# Mega8515_flasher_v2.net
KiCad netlist of a schematic drawn in EAGLE
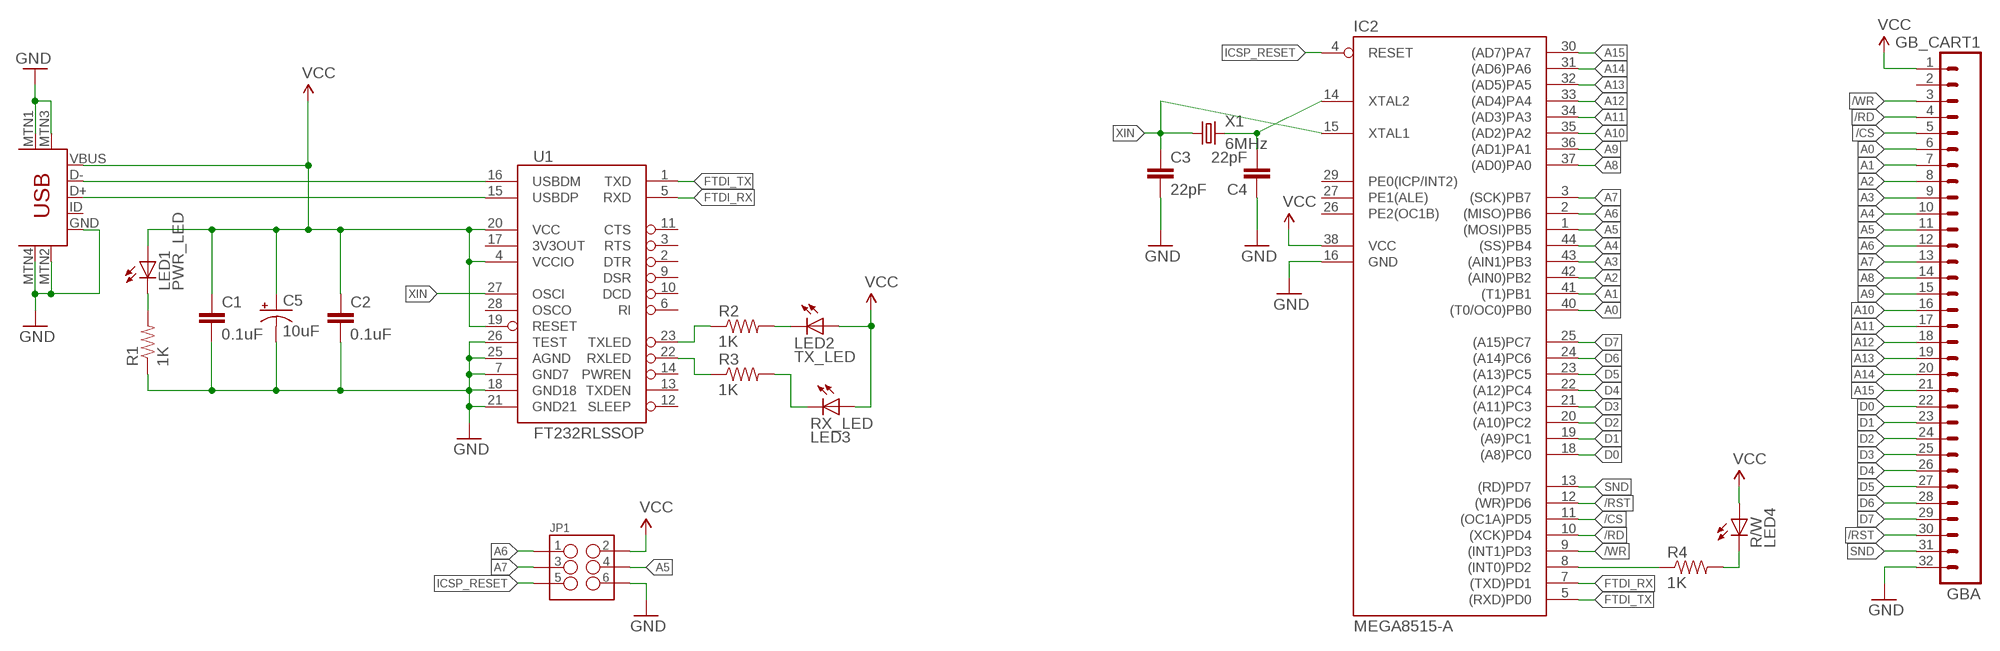
[diagram p0: schematic, sheet 1]

(export (version "E")
  (design (tool "Eeschema 10.0.6"))
  (components
    (comp (ref "C1")
      (value "0.1uF")
      (footprint "eagle-import:1206")
      (libsource (lib "eagle-import") (part "CAP1206"))
    )
    (comp (ref "C2")
      (value "0.1uF")
      (footprint "eagle-import:1206")
      (libsource (lib "eagle-import") (part "CAP1206"))
    )
    (comp (ref "C3")
      (value "22pF")
      (footprint "eagle-import:0805")
      (libsource (lib "eagle-import") (part "CAP0805"))
    )
    (comp (ref "C4")
      (value "22pF")
      (footprint "eagle-import:0805")
      (libsource (lib "eagle-import") (part "CAP0805"))
    )
    (comp (ref "C5")
      (value "10uF")
      (footprint "eagle-import:EIA3216")
      (libsource (lib "eagle-import") (part "10UF-TANT"))
    )
    (comp (ref "GBA")
      (value "GB_CART1")
      (footprint "eagle-import:GB_CART_1")
      (libsource (lib "eagle-import") (part "GB_CART1"))
    )
    (comp (ref "IC2")
      (value "MEGA8515-A")
      (footprint "eagle-import:TQFP44")
      (fields (field (name "MPN") "ATMEGA8515-16AU"))
      (libsource (lib "eagle-import") (part "MEGA8515-A"))
    )
    (comp (ref "JP1")
      (value "SPARKFUN-CONNECTORS_M03X2SMT")
      (footprint "eagle-import:SPARKFUN-CONNECTORS_2X3_SMT_POSTS")
      (libsource (lib "eagle-import") (part "SPARKFUN-CONNECTORS_M03X2SMT"))
    )
    (comp (ref "LED1")
      (value "PWR_LED")
      (footprint "eagle-import:LED-1206")
      (libsource (lib "eagle-import") (part "LED1206"))
    )
    (comp (ref "LED2")
      (value "TX_LED")
      (footprint "eagle-import:LED-1206")
      (libsource (lib "eagle-import") (part "LED1206"))
    )
    (comp (ref "R/W")
      (value "LED4")
      (footprint "eagle-import:LED-1206")
      (libsource (lib "eagle-import") (part "LED1206"))
    )
    (comp (ref "R1")
      (value "1K")
      (footprint "eagle-import:1206")
      (libsource (lib "eagle-import") (part "RESISTOR1206"))
    )
    (comp (ref "R2")
      (value "1K")
      (footprint "eagle-import:1206")
      (libsource (lib "eagle-import") (part "RESISTOR1206"))
    )
    (comp (ref "R3")
      (value "1K")
      (footprint "eagle-import:1206")
      (libsource (lib "eagle-import") (part "RESISTOR1206"))
    )
    (comp (ref "R4")
      (value "1K")
      (footprint "eagle-import:1206")
      (libsource (lib "eagle-import") (part "RESISTOR1206"))
    )
    (comp (ref "RX_LED")
      (value "LED3")
      (footprint "eagle-import:LED-1206")
      (libsource (lib "eagle-import") (part "LED1206"))
    )
    (comp (ref "U1")
      (value "FT232RLSSOP")
      (footprint "eagle-import:SSOP28DB")
      (libsource (lib "eagle-import") (part "FT232RLSSOP"))
    )
    (comp (ref "USB")
      (value "USB-MINIB-5PIN")
      (footprint "eagle-import:USB-MINIB")
      (libsource (lib "eagle-import") (part "USB-MINIB-5PIN"))
    )
    (comp (ref "X1")
      (value "6MHz")
      (footprint "eagle-import:SPARKFUN-FREQCTRL_CRYSTAL-SMD-11.8X5.5")
      (libsource (lib "eagle-import") (part "SPARKFUN-FREQCTRL_CRYSTAL"))
    )
  )
  (nets
    (net (code "1") (name "A0") (class "Default")
      (node (ref "GBA") (pin "6") (pinfunction "6_6") (pintype "passive"))
      (node (ref "IC2") (pin "40") (pinfunction "(T0/OC0)PB0_40") (pintype "bidirectional"))
    )
    (net (code "2") (name "A1") (class "Default")
      (node (ref "GBA") (pin "7") (pinfunction "7_7") (pintype "passive"))
      (node (ref "IC2") (pin "41") (pinfunction "(T1)PB1_41") (pintype "bidirectional"))
    )
    (net (code "3") (name "A2") (class "Default")
      (node (ref "GBA") (pin "8") (pinfunction "8_8") (pintype "passive"))
      (node (ref "IC2") (pin "42") (pinfunction "(AIN0)PB2_42") (pintype "bidirectional"))
    )
    (net (code "4") (name "A3") (class "Default")
      (node (ref "GBA") (pin "9") (pinfunction "9_9") (pintype "passive"))
      (node (ref "IC2") (pin "43") (pinfunction "(AIN1)PB3_43") (pintype "bidirectional"))
    )
    (net (code "5") (name "A4") (class "Default")
      (node (ref "GBA") (pin "10") (pinfunction "10_10") (pintype "passive"))
      (node (ref "IC2") (pin "44") (pinfunction "(SS)PB4_44") (pintype "bidirectional"))
    )
    (net (code "6") (name "A5") (class "Default")
      (node (ref "GBA") (pin "11") (pinfunction "11_11") (pintype "passive"))
      (node (ref "IC2") (pin "1") (pinfunction "(MOSI)PB5_1") (pintype "bidirectional"))
      (node (ref "JP1") (pin "4") (pinfunction "4_4") (pintype "bidirectional"))
    )
    (net (code "7") (name "A6") (class "Default")
      (node (ref "GBA") (pin "12") (pinfunction "12_12") (pintype "passive"))
      (node (ref "IC2") (pin "2") (pinfunction "(MISO)PB6_2") (pintype "bidirectional"))
      (node (ref "JP1") (pin "1") (pinfunction "1_1") (pintype "bidirectional"))
    )
    (net (code "8") (name "A7") (class "Default")
      (node (ref "GBA") (pin "13") (pinfunction "13_13") (pintype "passive"))
      (node (ref "IC2") (pin "3") (pinfunction "(SCK)PB7_3") (pintype "bidirectional"))
      (node (ref "JP1") (pin "3") (pinfunction "3_3") (pintype "bidirectional"))
    )
    (net (code "9") (name "A8") (class "Default")
      (node (ref "GBA") (pin "14") (pinfunction "14_14") (pintype "passive"))
      (node (ref "IC2") (pin "37") (pinfunction "(AD0)PA0_37") (pintype "bidirectional"))
    )
    (net (code "10") (name "A9") (class "Default")
      (node (ref "GBA") (pin "15") (pinfunction "15_15") (pintype "passive"))
      (node (ref "IC2") (pin "36") (pinfunction "(AD1)PA1_36") (pintype "bidirectional"))
    )
    (net (code "11") (name "A10") (class "Default")
      (node (ref "GBA") (pin "16") (pinfunction "16_16") (pintype "passive"))
      (node (ref "IC2") (pin "35") (pinfunction "(AD2)PA2_35") (pintype "bidirectional"))
    )
    (net (code "12") (name "A11") (class "Default")
      (node (ref "GBA") (pin "17") (pinfunction "17_17") (pintype "passive"))
      (node (ref "IC2") (pin "34") (pinfunction "(AD3)PA3_34") (pintype "bidirectional"))
    )
    (net (code "13") (name "A12") (class "Default")
      (node (ref "GBA") (pin "18") (pinfunction "18_18") (pintype "passive"))
      (node (ref "IC2") (pin "33") (pinfunction "(AD4)PA4_33") (pintype "bidirectional"))
    )
    (net (code "14") (name "A13") (class "Default")
      (node (ref "GBA") (pin "19") (pinfunction "19_19") (pintype "passive"))
      (node (ref "IC2") (pin "32") (pinfunction "(AD5)PA5_32") (pintype "bidirectional"))
    )
    (net (code "15") (name "A14") (class "Default")
      (node (ref "GBA") (pin "20") (pinfunction "20_20") (pintype "passive"))
      (node (ref "IC2") (pin "31") (pinfunction "(AD6)PA6_31") (pintype "bidirectional"))
    )
    (net (code "16") (name "A15") (class "Default")
      (node (ref "GBA") (pin "21") (pinfunction "21_21") (pintype "passive"))
      (node (ref "IC2") (pin "30") (pinfunction "(AD7)PA7_30") (pintype "bidirectional"))
    )
    (net (code "17") (name "D0") (class "Default")
      (node (ref "GBA") (pin "22") (pinfunction "22_22") (pintype "passive"))
      (node (ref "IC2") (pin "18") (pinfunction "(A8)PC0_18") (pintype "bidirectional"))
    )
    (net (code "18") (name "D1") (class "Default")
      (node (ref "GBA") (pin "23") (pinfunction "23_23") (pintype "passive"))
      (node (ref "IC2") (pin "19") (pinfunction "(A9)PC1_19") (pintype "bidirectional"))
    )
    (net (code "19") (name "D2") (class "Default")
      (node (ref "GBA") (pin "24") (pinfunction "24_24") (pintype "passive"))
      (node (ref "IC2") (pin "20") (pinfunction "(A10)PC2_20") (pintype "bidirectional"))
    )
    (net (code "20") (name "D3") (class "Default")
      (node (ref "GBA") (pin "25") (pinfunction "25_25") (pintype "passive"))
      (node (ref "IC2") (pin "21") (pinfunction "(A11)PC3_21") (pintype "bidirectional"))
    )
    (net (code "21") (name "D4") (class "Default")
      (node (ref "GBA") (pin "26") (pinfunction "26_26") (pintype "passive"))
      (node (ref "IC2") (pin "22") (pinfunction "(A12)PC4_22") (pintype "bidirectional"))
    )
    (net (code "22") (name "D5") (class "Default")
      (node (ref "GBA") (pin "27") (pinfunction "27_27") (pintype "passive"))
      (node (ref "IC2") (pin "23") (pinfunction "(A13)PC5_23") (pintype "bidirectional"))
    )
    (net (code "23") (name "D6") (class "Default")
      (node (ref "GBA") (pin "28") (pinfunction "28_28") (pintype "passive"))
      (node (ref "IC2") (pin "24") (pinfunction "(A14)PC6_24") (pintype "bidirectional"))
    )
    (net (code "24") (name "D7") (class "Default")
      (node (ref "GBA") (pin "29") (pinfunction "29_29") (pintype "passive"))
      (node (ref "IC2") (pin "25") (pinfunction "(A15)PC7_25") (pintype "bidirectional"))
    )
    (net (code "25") (name "FTDI_RX") (class "Default")
      (node (ref "IC2") (pin "7") (pinfunction "(TXD)PD1_7") (pintype "bidirectional"))
      (node (ref "U1") (pin "5") (pinfunction "RXD_5") (pintype "input"))
    )
    (net (code "26") (name "FTDI_TX") (class "Default")
      (node (ref "IC2") (pin "5") (pinfunction "(RXD)PD0_5") (pintype "bidirectional"))
      (node (ref "U1") (pin "1") (pinfunction "TXD_1") (pintype "output"))
    )
    (net (code "27") (name "GND") (class "Default")
      (node (ref "C1") (pin "2") (pinfunction "2_2") (pintype "passive"))
      (node (ref "C2") (pin "2") (pinfunction "2_2") (pintype "passive"))
      (node (ref "C3") (pin "2") (pinfunction "2_2") (pintype "passive"))
      (node (ref "C4") (pin "1") (pinfunction "1_1") (pintype "passive"))
      (node (ref "C5") (pin "C") (pinfunction "-_C") (pintype "passive"))
      (node (ref "GBA") (pin "32") (pinfunction "32_32") (pintype "passive"))
      (node (ref "IC2") (pin "16") (pinfunction "GND_16") (pintype "power_in"))
      (node (ref "JP1") (pin "6") (pinfunction "6_6") (pintype "bidirectional"))
      (node (ref "R1") (pin "1") (pinfunction "1_1") (pintype "passive"))
      (node (ref "U1") (pin "18") (pinfunction "GND18_18") (pintype "power_in"))
      (node (ref "U1") (pin "21") (pinfunction "GND21_21") (pintype "power_in"))
      (node (ref "U1") (pin "25") (pinfunction "AGND_25") (pintype "power_in"))
      (node (ref "U1") (pin "26") (pinfunction "TEST_26") (pintype "input"))
      (node (ref "U1") (pin "7") (pinfunction "GND7_7") (pintype "power_in"))
      (node (ref "USB") (pin "GND") (pinfunction "GND_GND") (pintype "bidirectional"))
      (node (ref "USB") (pin "MTN1") (pinfunction "MTN2_MTN1") (pintype "bidirectional"))
      (node (ref "USB") (pin "MTN2") (pinfunction "MTN3_MTN2") (pintype "bidirectional"))
      (node (ref "USB") (pin "MTN3") (pinfunction "MTN1_MTN3") (pintype "bidirectional"))
      (node (ref "USB") (pin "MTN4") (pinfunction "MTN4_MTN4") (pintype "bidirectional"))
    )
    (net (code "28") (name "ICSP_RESET") (class "Default")
      (node (ref "IC2") (pin "4") (pinfunction "RESET_4") (pintype "input"))
      (node (ref "JP1") (pin "5") (pinfunction "5_5") (pintype "bidirectional"))
    )
    (net (code "29") (name "Net-(IC2-(INT0)PD2)") (class "Default")
      (node (ref "IC2") (pin "8") (pinfunction "(INT0)PD2_8") (pintype "bidirectional"))
      (node (ref "R4") (pin "1") (pinfunction "1_1") (pintype "passive"))
    )
    (net (code "30") (name "Net-(IC2-XTAL2)") (class "Default")
      (node (ref "C4") (pin "2") (pinfunction "2_2") (pintype "passive"))
      (node (ref "IC2") (pin "14") (pinfunction "XTAL2_14") (pintype "bidirectional"))
      (node (ref "X1") (pin "2") (pinfunction "2_2") (pintype "passive"))
      (node (ref "X1") (pin "3") (pinfunction "2_3") (pintype "passive"))
    )
    (net (code "31") (name "Net-(LED1-PadC)") (class "Default")
      (node (ref "LED1") (pin "C") (pinfunction "C_C") (pintype "passive"))
      (node (ref "R1") (pin "2") (pinfunction "2_2") (pintype "passive"))
    )
    (net (code "32") (name "Net-(LED2-PadC)") (class "Default")
      (node (ref "LED2") (pin "C") (pinfunction "C_C") (pintype "passive"))
      (node (ref "R2") (pin "2") (pinfunction "2_2") (pintype "passive"))
    )
    (net (code "33") (name "Net-(R/W-PadC)") (class "Default")
      (node (ref "R/W") (pin "C") (pinfunction "C_C") (pintype "passive"))
      (node (ref "R4") (pin "2") (pinfunction "2_2") (pintype "passive"))
    )
    (net (code "34") (name "Net-(R3-Pad2)") (class "Default")
      (node (ref "R3") (pin "2") (pinfunction "2_2") (pintype "passive"))
      (node (ref "RX_LED") (pin "C") (pinfunction "C_C") (pintype "passive"))
    )
    (net (code "35") (name "Net-(U1-RXLED)") (class "Default")
      (node (ref "R3") (pin "1") (pinfunction "1_1") (pintype "passive"))
      (node (ref "U1") (pin "22") (pinfunction "RXLED_22") (pintype "input"))
    )
    (net (code "36") (name "Net-(U1-TXLED)") (class "Default")
      (node (ref "R2") (pin "1") (pinfunction "1_1") (pintype "passive"))
      (node (ref "U1") (pin "23") (pinfunction "TXLED_23") (pintype "input"))
    )
    (net (code "37") (name "Net-(U1-USBDM)") (class "Default")
      (node (ref "U1") (pin "16") (pinfunction "USBDM_16") (pintype "bidirectional"))
      (node (ref "USB") (pin "D-") (pinfunction "D-_D-") (pintype "bidirectional"))
    )
    (net (code "38") (name "Net-(U1-USBDP)") (class "Default")
      (node (ref "U1") (pin "15") (pinfunction "USBDP_15") (pintype "bidirectional"))
      (node (ref "USB") (pin "D+") (pinfunction "D+_D+") (pintype "bidirectional"))
    )
    (net (code "39") (name "SND") (class "Default")
      (node (ref "GBA") (pin "31") (pinfunction "31_31") (pintype "passive"))
      (node (ref "IC2") (pin "13") (pinfunction "(RD)PD7_13") (pintype "bidirectional"))
    )
    (net (code "40") (name "VCC") (class "Default")
      (node (ref "C1") (pin "1") (pinfunction "1_1") (pintype "passive"))
      (node (ref "C2") (pin "1") (pinfunction "1_1") (pintype "passive"))
      (node (ref "C5") (pin "A") (pinfunction "+_A") (pintype "passive"))
      (node (ref "GBA") (pin "1") (pinfunction "1_1") (pintype "passive"))
      (node (ref "IC2") (pin "38") (pinfunction "VCC_38") (pintype "power_in"))
      (node (ref "JP1") (pin "2") (pinfunction "2_2") (pintype "bidirectional"))
      (node (ref "LED1") (pin "A") (pinfunction "A_A") (pintype "passive"))
      (node (ref "LED2") (pin "A") (pinfunction "A_A") (pintype "passive"))
      (node (ref "R/W") (pin "A") (pinfunction "A_A") (pintype "passive"))
      (node (ref "RX_LED") (pin "A") (pinfunction "A_A") (pintype "passive"))
      (node (ref "U1") (pin "19") (pinfunction "RESET_19") (pintype "input"))
      (node (ref "U1") (pin "20") (pinfunction "VCC_20") (pintype "power_in"))
      (node (ref "U1") (pin "4") (pinfunction "VCCIO_4") (pintype "power_in"))
      (node (ref "USB") (pin "VBUS") (pinfunction "VBUS_VBUS") (pintype "bidirectional"))
    )
    (net (code "41") (name "XIN") (class "Default")
      (node (ref "C3") (pin "1") (pinfunction "1_1") (pintype "passive"))
      (node (ref "IC2") (pin "15") (pinfunction "XTAL1_15") (pintype "bidirectional"))
      (node (ref "U1") (pin "27") (pinfunction "OSCI_27") (pintype "input"))
      (node (ref "X1") (pin "1") (pinfunction "1_1") (pintype "passive"))
      (node (ref "X1") (pin "4") (pinfunction "1_4") (pintype "passive"))
    )
    (net (code "42") (name "unconnected-(GBA-Pad2)") (class "Default")
      (node (ref "GBA") (pin "2") (pinfunction "2_2") (pintype "passive"))
    )
    (net (code "43") (name "unconnected-(IC2-NC1-Pad6)") (class "Default")
      (node (ref "IC2") (pin "6") (pinfunction "NC1_6") (pintype "no_connect"))
    )
    (net (code "44") (name "unconnected-(IC2-NC2-Pad17)") (class "Default")
      (node (ref "IC2") (pin "17") (pinfunction "NC2_17") (pintype "no_connect"))
    )
    (net (code "45") (name "unconnected-(IC2-NC3-Pad28)") (class "Default")
      (node (ref "IC2") (pin "28") (pinfunction "NC3_28") (pintype "no_connect"))
    )
    (net (code "46") (name "unconnected-(IC2-NC4-Pad39)") (class "Default")
      (node (ref "IC2") (pin "39") (pinfunction "NC4_39") (pintype "no_connect"))
    )
    (net (code "47") (name "unconnected-(IC2-PE0(ICP{slash}INT2)-Pad29)") (class "Default")
      (node (ref "IC2") (pin "29") (pinfunction "PE0(ICP/INT2)_29") (pintype "bidirectional"))
    )
    (net (code "48") (name "unconnected-(IC2-PE1(ALE)-Pad27)") (class "Default")
      (node (ref "IC2") (pin "27") (pinfunction "PE1(ALE)_27") (pintype "bidirectional"))
    )
    (net (code "49") (name "unconnected-(IC2-PE2(OC1B)-Pad26)") (class "Default")
      (node (ref "IC2") (pin "26") (pinfunction "PE2(OC1B)_26") (pintype "bidirectional"))
    )
    (net (code "50") (name "unconnected-(U1-3V3OUT-Pad17)") (class "Default")
      (node (ref "U1") (pin "17") (pinfunction "3V3OUT_17") (pintype "output"))
    )
    (net (code "51") (name "unconnected-(U1-CTS-Pad11)") (class "Default")
      (node (ref "U1") (pin "11") (pinfunction "CTS_11") (pintype "input"))
    )
    (net (code "52") (name "unconnected-(U1-DCD-Pad10)") (class "Default")
      (node (ref "U1") (pin "10") (pinfunction "DCD_10") (pintype "input"))
    )
    (net (code "53") (name "unconnected-(U1-DSR-Pad9)") (class "Default")
      (node (ref "U1") (pin "9") (pinfunction "DSR_9") (pintype "input"))
    )
    (net (code "54") (name "unconnected-(U1-DTR-Pad2)") (class "Default")
      (node (ref "U1") (pin "2") (pinfunction "DTR_2") (pintype "output"))
    )
    (net (code "55") (name "unconnected-(U1-OSCO-Pad28)") (class "Default")
      (node (ref "U1") (pin "28") (pinfunction "OSCO_28") (pintype "output"))
    )
    (net (code "56") (name "unconnected-(U1-PWREN-Pad14)") (class "Default")
      (node (ref "U1") (pin "14") (pinfunction "PWREN_14") (pintype "input"))
    )
    (net (code "57") (name "unconnected-(U1-RI-Pad6)") (class "Default")
      (node (ref "U1") (pin "6") (pinfunction "RI_6") (pintype "input"))
    )
    (net (code "58") (name "unconnected-(U1-RTS-Pad3)") (class "Default")
      (node (ref "U1") (pin "3") (pinfunction "RTS_3") (pintype "output"))
    )
    (net (code "59") (name "unconnected-(U1-SLEEP-Pad12)") (class "Default")
      (node (ref "U1") (pin "12") (pinfunction "SLEEP_12") (pintype "input"))
    )
    (net (code "60") (name "unconnected-(U1-TXDEN-Pad13)") (class "Default")
      (node (ref "U1") (pin "13") (pinfunction "TXDEN_13") (pintype "input"))
    )
    (net (code "61") (name "unconnected-(USB-PadID)") (class "Default")
      (node (ref "USB") (pin "ID") (pinfunction "ID_ID") (pintype "bidirectional"))
    )
    (net (code "62") (name "{slash}CS") (class "Default")
      (node (ref "GBA") (pin "5") (pinfunction "5_5") (pintype "passive"))
      (node (ref "IC2") (pin "11") (pinfunction "(OC1A)PD5_11") (pintype "bidirectional"))
    )
    (net (code "63") (name "{slash}RD") (class "Default")
      (node (ref "GBA") (pin "4") (pinfunction "4_4") (pintype "passive"))
      (node (ref "IC2") (pin "10") (pinfunction "(XCK)PD4_10") (pintype "bidirectional"))
    )
    (net (code "64") (name "{slash}RST") (class "Default")
      (node (ref "GBA") (pin "30") (pinfunction "30_30") (pintype "passive"))
      (node (ref "IC2") (pin "12") (pinfunction "(WR)PD6_12") (pintype "bidirectional"))
    )
    (net (code "65") (name "{slash}WR") (class "Default")
      (node (ref "GBA") (pin "3") (pinfunction "3_3") (pintype "passive"))
      (node (ref "IC2") (pin "9") (pinfunction "(INT1)PD3_9") (pintype "bidirectional"))
    )
  )
)
